# Indicator_voltage_TNN_V1_0.net
KiCad netlist of a schematic drawn in EAGLE
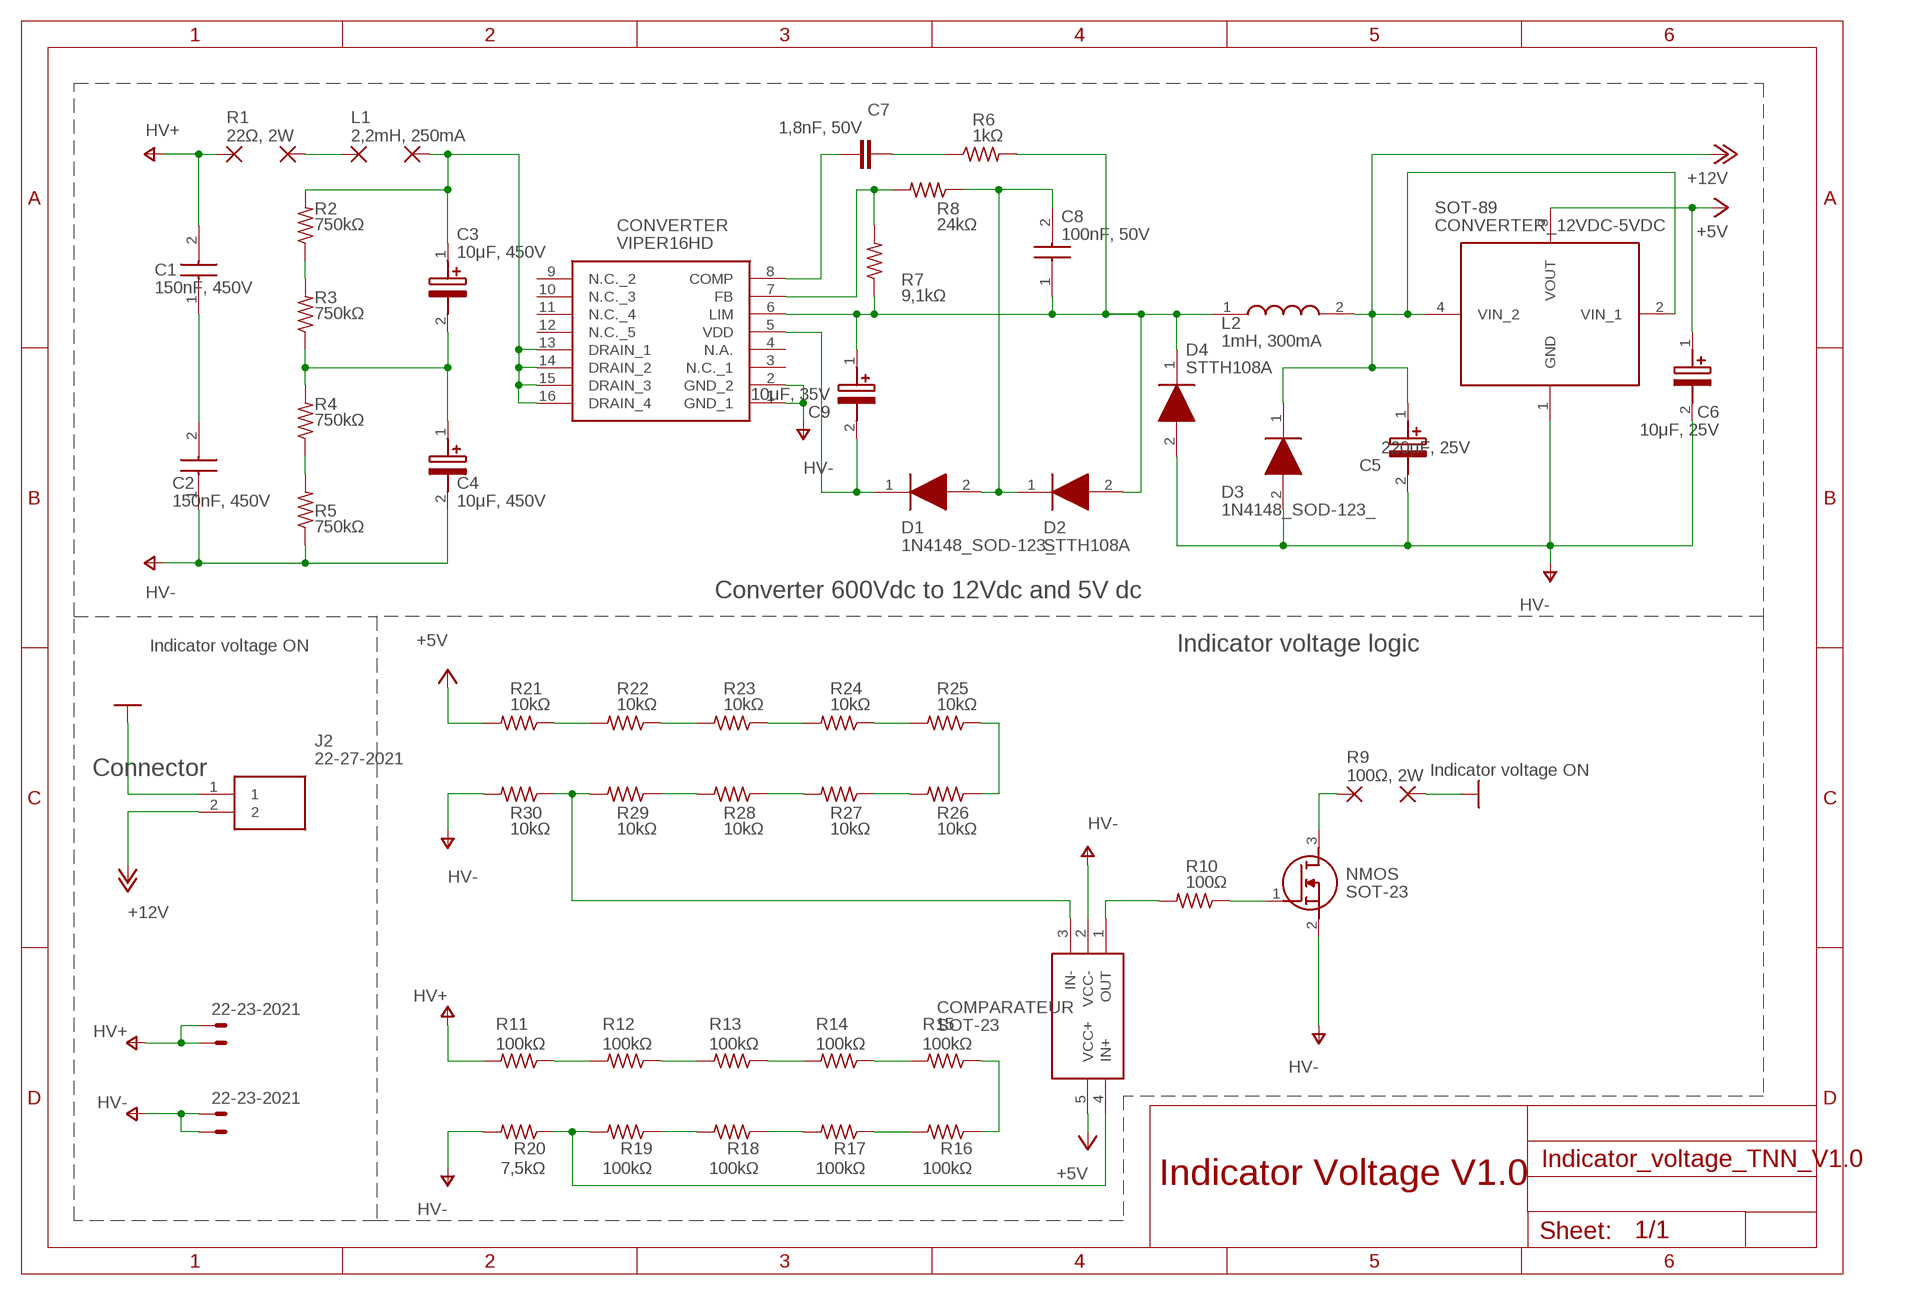
[diagram p0: schematic, sheet 1]

(export (version "E")
  (design (tool "Eeschema 10.0.6"))
  (components
    (comp (ref "C1")
      (value "150nF, 450V")
      (footprint "eagle-import:CAPC4720X175N")
      (fields
        (field (name "ARROW_PART_NUMBER") "C1808W154KCRACTU")
        (field (name "MOUSER_PART_NUMBER") "80-C1808W154KCR")
      )
      (libsource (lib "eagle-import") (part "C1808W154KCRACTU"))
    )
    (comp (ref "C2")
      (value "150nF, 450V")
      (footprint "eagle-import:CAPC4720X175N")
      (fields
        (field (name "ARROW_PART_NUMBER") "C1808W154KCRACTU")
        (field (name "MOUSER_PART_NUMBER") "80-C1808W154KCR")
      )
      (libsource (lib "eagle-import") (part "C1808W154KCRACTU"))
    )
    (comp (ref "C3")
      (value "10μF, 450V")
      (footprint "eagle-import:CAPPRD500W60D1300H2250")
      (fields (field (name "MANUFACTURER_PART_NUMBER") "7112129"))
      (libsource (lib "eagle-import") (part "7112129"))
    )
    (comp (ref "C4")
      (value "10μF, 450V")
      (footprint "eagle-import:CAPPRD500W60D1300H2250")
      (fields (field (name "MANUFACTURER_PART_NUMBER") "7112129"))
      (libsource (lib "eagle-import") (part "7112129"))
    )
    (comp (ref "C5")
      (value "220μF, 25V")
      (footprint "eagle-import:CAPPRD500W60D1300H2250")
      (fields (field (name "MANUFACTURER_PART_NUMBER") "7112129"))
      (libsource (lib "eagle-import") (part "7112129"))
    )
    (comp (ref "C6")
      (value "10μF, 25V")
      (footprint "eagle-import:CAPPRD200W55D525H1200")
      (fields (field (name "MANUFACTURER_PART_NUMBER") "ECA1VM100"))
      (libsource (lib "eagle-import") (part "ECA1VM100"))
    )
    (comp (ref "C7")
      (value "1,8nF, 50V")
      (footprint "eagle-import:C0805")
      (libsource (lib "eagle-import") (part "C-EUC0805"))
    )
    (comp (ref "C8")
      (value "100nF, 50V")
      (footprint "eagle-import:CAPC2012X88N")
      (fields
        (field (name "ARROW_PART_NUMBER") "C0805C104K5RACTU")
        (field (name "MOUSER_PART_NUMBER") "80-C0805C104K5R")
      )
      (libsource (lib "eagle-import") (part "C0805C104K5RACTU"))
    )
    (comp (ref "C9")
      (value "10μF, 35V")
      (footprint "eagle-import:CAPPRD200W55D525H1200")
      (fields (field (name "MANUFACTURER_PART_NUMBER") "ECA1VM100"))
      (libsource (lib "eagle-import") (part "ECA1VM100"))
    )
    (comp (ref "COMPARATEUR")
      (value "SOT-23")
      (footprint "eagle-import:SOT95P280X145-5N")
      (fields
        (field (name "ARROW_PART_NUMBER") "TS391IYLT")
        (field (name "MOUSER_PART_NUMBER") "511-TS391IYLT")
      )
      (libsource (lib "eagle-import") (part "TS391IYLT"))
    )
    (comp (ref "CONVERTER")
      (value "VIPER16HD")
      (footprint "eagle-import:SOIC127P600X175-16N")
      (fields (field (name "MOUSER_PART_NUMBER") "511-VIPER16HD"))
      (libsource (lib "eagle-import") (part "VIPER16HD"))
    )
    (comp (ref "CONVERTER_12VDC-5VDC")
      (value "SOT-89")
      (footprint "eagle-import:ST-SOT-89")
      (fields
        (field (name "ARROW_PART_NUMBER") "LDK320ADU120R")
        (field (name "MOUSER_PART_NUMBER") "511-LDK320ADU120R")
      )
      (libsource (lib "eagle-import") (part "LDK320ADU120R"))
    )
    (comp (ref "D1")
      (value "1N4148_SOD-123_")
      (footprint "eagle-import:SOD3716X135N")
      (fields (field (name "MANUFACTURER_PART_NUMBER") "1N4148(SOD-123)"))
      (libsource (lib "eagle-import") (part "1N4148_SOD-123_"))
    )
    (comp (ref "D2")
      (value "STTH108A")
      (footprint "eagle-import:DIOM5126X265N")
      (fields (field (name "MOUSER_PART_NUMBER") "511-STTH108A"))
      (libsource (lib "eagle-import") (part "STTH108A"))
    )
    (comp (ref "D3")
      (value "1N4148_SOD-123_")
      (footprint "eagle-import:SOD3716X135N")
      (fields (field (name "MANUFACTURER_PART_NUMBER") "1N4148(SOD-123)"))
      (libsource (lib "eagle-import") (part "1N4148_SOD-123_"))
    )
    (comp (ref "D4")
      (value "STTH108A")
      (footprint "eagle-import:DIOM5126X265N")
      (fields (field (name "MOUSER_PART_NUMBER") "511-STTH108A"))
      (libsource (lib "eagle-import") (part "STTH108A"))
    )
    (comp (ref "HV+")
      (value "22-23-2021")
      (footprint "eagle-import:22-23-2021")
      (fields (field (name "MF") "MOLEX"))
      (libsource (lib "eagle-import") (part "22-23-2021"))
    )
    (comp (ref "HV-")
      (value "22-23-2021")
      (footprint "eagle-import:22-23-2021")
      (fields (field (name "MF") "MOLEX"))
      (libsource (lib "eagle-import") (part "22-23-2021"))
    )
    (comp (ref "J2")
      (value "22-27-2021")
      (footprint "eagle-import:SHDR2W64P0X254_1X2_508X580X117")
      (fields (field (name "MOUSER_PART_NUMBER") "538-22-27-2021"))
      (libsource (lib "eagle-import") (part "22-27-2021"))
    )
    (comp (ref "L1")
      (value "2,2mH, 250mA")
      (footprint "eagle-import:1,6_0,8")
      (libsource (lib "eagle-import") (part "1,6/0,8"))
    )
    (comp (ref "L2")
      (value "1mH, 300mA")
      (footprint "eagle-import:RLB0914")
      (fields
        (field (name "ARROW_PART_NUMBER") "RLB0914-102KL")
        (field (name "MOUSER_PART_NUMBER") "652-RLB0914-102KL")
      )
      (libsource (lib "eagle-import") (part "RLB0914-102KL"))
    )
    (comp (ref "L3")
      (value "2,2mH, 250mA")
      (footprint "eagle-import:1,6_0,8")
      (libsource (lib "eagle-import") (part "1,6/0,8"))
    )
    (comp (ref "NMOS")
      (value "SOT-23")
      (footprint "eagle-import:SOT96P240X110-3N")
      (fields
        (field (name "ARROW_PART_NUMBER") "DMN2041L-7")
        (field (name "MOUSER_PART_NUMBER") "621-DMN2041L-7")
      )
      (libsource (lib "eagle-import") (part "DMN2041L-7"))
    )
    (comp (ref "PAD2")
      (value "1,6/0,8")
      (footprint "eagle-import:1,6_0,8")
      (libsource (lib "eagle-import") (part "1,6/0,8"))
    )
    (comp (ref "PAD4")
      (value "1,6/0,8")
      (footprint "eagle-import:1,6_0,8")
      (libsource (lib "eagle-import") (part "1,6/0,8"))
    )
    (comp (ref "R1")
      (value "22Ω, 2W")
      (footprint "eagle-import:1,6_0,8")
      (libsource (lib "eagle-import") (part "1,6/0,8"))
    )
    (comp (ref "R2")
      (value "750kΩ")
      (footprint "eagle-import:M3216")
      (libsource (lib "eagle-import") (part "R-US_M3216"))
    )
    (comp (ref "R3")
      (value "750kΩ")
      (footprint "eagle-import:M3216")
      (libsource (lib "eagle-import") (part "R-US_M3216"))
    )
    (comp (ref "R4")
      (value "750kΩ")
      (footprint "eagle-import:M3216")
      (libsource (lib "eagle-import") (part "R-US_M3216"))
    )
    (comp (ref "R5")
      (value "750kΩ")
      (footprint "eagle-import:M3216")
      (libsource (lib "eagle-import") (part "R-US_M3216"))
    )
    (comp (ref "R6")
      (value "1kΩ")
      (footprint "eagle-import:M2012")
      (libsource (lib "eagle-import") (part "R-US_M2012"))
    )
    (comp (ref "R7")
      (value "9,1kΩ")
      (footprint "eagle-import:M2012")
      (libsource (lib "eagle-import") (part "R-US_M2012"))
    )
    (comp (ref "R8")
      (value "24kΩ")
      (footprint "eagle-import:M2012")
      (libsource (lib "eagle-import") (part "R-US_M2012"))
    )
    (comp (ref "R9")
      (value "100Ω, 2W")
      (footprint "eagle-import:1,6_0,8")
      (libsource (lib "eagle-import") (part "1,6/0,8"))
    )
    (comp (ref "R10")
      (value "100Ω")
      (footprint "eagle-import:R0603")
      (libsource (lib "eagle-import") (part "R-US_R0603"))
    )
    (comp (ref "R11")
      (value "100kΩ")
      (footprint "eagle-import:R0603")
      (libsource (lib "eagle-import") (part "R-US_R0603"))
    )
    (comp (ref "R12")
      (value "100kΩ")
      (footprint "eagle-import:R0603")
      (libsource (lib "eagle-import") (part "R-US_R0603"))
    )
    (comp (ref "R13")
      (value "100kΩ")
      (footprint "eagle-import:R0603")
      (libsource (lib "eagle-import") (part "R-US_R0603"))
    )
    (comp (ref "R14")
      (value "100kΩ")
      (footprint "eagle-import:R0603")
      (libsource (lib "eagle-import") (part "R-US_R0603"))
    )
    (comp (ref "R15")
      (value "100kΩ")
      (footprint "eagle-import:R0603")
      (libsource (lib "eagle-import") (part "R-US_R0603"))
    )
    (comp (ref "R16")
      (value "100kΩ")
      (footprint "eagle-import:R0603")
      (libsource (lib "eagle-import") (part "R-US_R0603"))
    )
    (comp (ref "R17")
      (value "100kΩ")
      (footprint "eagle-import:R0603")
      (libsource (lib "eagle-import") (part "R-US_R0603"))
    )
    (comp (ref "R18")
      (value "100kΩ")
      (footprint "eagle-import:R0603")
      (libsource (lib "eagle-import") (part "R-US_R0603"))
    )
    (comp (ref "R19")
      (value "100kΩ")
      (footprint "eagle-import:R0603")
      (libsource (lib "eagle-import") (part "R-US_R0603"))
    )
    (comp (ref "R20")
      (value "7,5kΩ")
      (footprint "eagle-import:R0603")
      (libsource (lib "eagle-import") (part "R-US_R0603"))
    )
    (comp (ref "R21")
      (value "10kΩ")
      (footprint "eagle-import:R0603")
      (libsource (lib "eagle-import") (part "R-US_R0603"))
    )
    (comp (ref "R22")
      (value "10kΩ")
      (footprint "eagle-import:R0603")
      (libsource (lib "eagle-import") (part "R-US_R0603"))
    )
    (comp (ref "R23")
      (value "10kΩ")
      (footprint "eagle-import:R0603")
      (libsource (lib "eagle-import") (part "R-US_R0603"))
    )
    (comp (ref "R24")
      (value "10kΩ")
      (footprint "eagle-import:R0603")
      (libsource (lib "eagle-import") (part "R-US_R0603"))
    )
    (comp (ref "R25")
      (value "10kΩ")
      (footprint "eagle-import:R0603")
      (libsource (lib "eagle-import") (part "R-US_R0603"))
    )
    (comp (ref "R26")
      (value "10kΩ")
      (footprint "eagle-import:R0603")
      (libsource (lib "eagle-import") (part "R-US_R0603"))
    )
    (comp (ref "R27")
      (value "10kΩ")
      (footprint "eagle-import:R0603")
      (libsource (lib "eagle-import") (part "R-US_R0603"))
    )
    (comp (ref "R28")
      (value "10kΩ")
      (footprint "eagle-import:R0603")
      (libsource (lib "eagle-import") (part "R-US_R0603"))
    )
    (comp (ref "R29")
      (value "10kΩ")
      (footprint "eagle-import:R0603")
      (libsource (lib "eagle-import") (part "R-US_R0603"))
    )
    (comp (ref "R30")
      (value "10kΩ")
      (footprint "eagle-import:R0603")
      (libsource (lib "eagle-import") (part "R-US_R0603"))
    )
  )
  (nets
    (net (code "1") (name "+5V") (class "Default")
      (node (ref "C6") (pin "1") (pinfunction "+_1") (pintype "bidirectional"))
      (node (ref "COMPARATEUR") (pin "5") (pinfunction "VCC+_5") (pintype "bidirectional"))
      (node (ref "CONVERTER_12VDC-5VDC") (pin "3") (pinfunction "VOUT_3") (pintype "bidirectional"))
      (node (ref "R21") (pin "2") (pinfunction "2_2") (pintype "passive"))
    )
    (net (code "2") (name "+12V") (class "Default")
      (node (ref "C5") (pin "1") (pinfunction "+_1") (pintype "bidirectional"))
      (node (ref "CONVERTER_12VDC-5VDC") (pin "2") (pinfunction "VIN_1_2") (pintype "bidirectional"))
      (node (ref "CONVERTER_12VDC-5VDC") (pin "4") (pinfunction "VIN_2_4") (pintype "bidirectional"))
      (node (ref "D3") (pin "1") (pinfunction "K_1") (pintype "bidirectional"))
      (node (ref "J2") (pin "2") (pinfunction "2_2") (pintype "bidirectional"))
      (node (ref "L2") (pin "2") (pinfunction "2_2") (pintype "bidirectional"))
    )
    (net (code "3") (name "HV+") (class "Default")
      (node (ref "C1") (pin "2") (pinfunction "2_2") (pintype "bidirectional"))
      (node (ref "HV+") (pin "1") (pinfunction "S_1") (pintype "passive"))
      (node (ref "HV+") (pin "2") (pinfunction "S_2") (pintype "passive"))
      (node (ref "R1") (pin "1") (pinfunction "P_1") (pintype "passive"))
      (node (ref "R11") (pin "2") (pinfunction "2_2") (pintype "passive"))
    )
    (net (code "4") (name "HV-") (class "Default")
      (node (ref "C2") (pin "1") (pinfunction "1_1") (pintype "bidirectional"))
      (node (ref "C4") (pin "2") (pinfunction "-_2") (pintype "bidirectional"))
      (node (ref "C5") (pin "2") (pinfunction "-_2") (pintype "bidirectional"))
      (node (ref "C6") (pin "2") (pinfunction "-_2") (pintype "bidirectional"))
      (node (ref "COMPARATEUR") (pin "2") (pinfunction "VCC-_2") (pintype "bidirectional"))
      (node (ref "CONVERTER") (pin "1") (pinfunction "GND_1_1") (pintype "bidirectional"))
      (node (ref "CONVERTER") (pin "2") (pinfunction "GND_2_2") (pintype "bidirectional"))
      (node (ref "CONVERTER_12VDC-5VDC") (pin "1") (pinfunction "GND_1") (pintype "bidirectional"))
      (node (ref "D3") (pin "2") (pinfunction "A_2") (pintype "bidirectional"))
      (node (ref "D4") (pin "2") (pinfunction "A_2") (pintype "bidirectional"))
      (node (ref "HV-") (pin "1") (pinfunction "S_1") (pintype "passive"))
      (node (ref "HV-") (pin "2") (pinfunction "S_2") (pintype "passive"))
      (node (ref "NMOS") (pin "2") (pinfunction "S_2") (pintype "bidirectional"))
      (node (ref "R20") (pin "2") (pinfunction "2_2") (pintype "passive"))
      (node (ref "R30") (pin "2") (pinfunction "2_2") (pintype "passive"))
      (node (ref "R5") (pin "1") (pinfunction "1_1") (pintype "passive"))
    )
    (net (code "5") (name "Indicator voltage ON") (class "Default")
      (node (ref "J2") (pin "1") (pinfunction "1_1") (pintype "bidirectional"))
      (node (ref "PAD4") (pin "1") (pinfunction "P_1") (pintype "passive"))
    )
    (net (code "6") (name "Net-(C1-Pad1)") (class "Default")
      (node (ref "C1") (pin "1") (pinfunction "1_1") (pintype "bidirectional"))
      (node (ref "C2") (pin "2") (pinfunction "2_2") (pintype "bidirectional"))
    )
    (net (code "7") (name "Net-(C3-+)") (class "Default")
      (node (ref "C3") (pin "1") (pinfunction "+_1") (pintype "bidirectional"))
      (node (ref "CONVERTER") (pin "13") (pinfunction "DRAIN_1_13") (pintype "bidirectional"))
      (node (ref "CONVERTER") (pin "14") (pinfunction "DRAIN_2_14") (pintype "bidirectional"))
      (node (ref "CONVERTER") (pin "15") (pinfunction "DRAIN_3_15") (pintype "bidirectional"))
      (node (ref "CONVERTER") (pin "16") (pinfunction "DRAIN_4_16") (pintype "bidirectional"))
      (node (ref "L3") (pin "1") (pinfunction "P_1") (pintype "passive"))
      (node (ref "R2") (pin "2") (pinfunction "2_2") (pintype "passive"))
    )
    (net (code "8") (name "Net-(C3--)") (class "Default")
      (node (ref "C3") (pin "2") (pinfunction "-_2") (pintype "bidirectional"))
      (node (ref "C4") (pin "1") (pinfunction "+_1") (pintype "bidirectional"))
      (node (ref "R3") (pin "1") (pinfunction "1_1") (pintype "passive"))
      (node (ref "R4") (pin "2") (pinfunction "2_2") (pintype "passive"))
    )
    (net (code "9") (name "Net-(C7-Pad1)") (class "Default")
      (node (ref "C7") (pin "1") (pinfunction "1_1") (pintype "passive"))
      (node (ref "R6") (pin "1") (pinfunction "1_1") (pintype "passive"))
    )
    (net (code "10") (name "Net-(C9-+)") (class "Default")
      (node (ref "C8") (pin "1") (pinfunction "1_1") (pintype "bidirectional"))
      (node (ref "C9") (pin "1") (pinfunction "+_1") (pintype "bidirectional"))
      (node (ref "CONVERTER") (pin "6") (pinfunction "LIM_6") (pintype "bidirectional"))
      (node (ref "D2") (pin "2") (pinfunction "A_2") (pintype "bidirectional"))
      (node (ref "D4") (pin "1") (pinfunction "K_1") (pintype "bidirectional"))
      (node (ref "L2") (pin "1") (pinfunction "1_1") (pintype "bidirectional"))
      (node (ref "R6") (pin "2") (pinfunction "2_2") (pintype "passive"))
      (node (ref "R7") (pin "1") (pinfunction "1_1") (pintype "passive"))
    )
    (net (code "11") (name "Net-(C9--)") (class "Default")
      (node (ref "C9") (pin "2") (pinfunction "-_2") (pintype "bidirectional"))
      (node (ref "CONVERTER") (pin "5") (pinfunction "VDD_5") (pintype "bidirectional"))
      (node (ref "D1") (pin "1") (pinfunction "K_1") (pintype "bidirectional"))
    )
    (net (code "12") (name "Net-(COMPARATEUR-IN+)") (class "Default")
      (node (ref "COMPARATEUR") (pin "4") (pinfunction "IN+_4") (pintype "bidirectional"))
      (node (ref "R19") (pin "2") (pinfunction "2_2") (pintype "passive"))
      (node (ref "R20") (pin "1") (pinfunction "1_1") (pintype "passive"))
    )
    (net (code "13") (name "Net-(COMPARATEUR-IN-)") (class "Default")
      (node (ref "COMPARATEUR") (pin "3") (pinfunction "IN-_3") (pintype "bidirectional"))
      (node (ref "R29") (pin "2") (pinfunction "2_2") (pintype "passive"))
      (node (ref "R30") (pin "1") (pinfunction "1_1") (pintype "passive"))
    )
    (net (code "14") (name "Net-(COMPARATEUR-OUT)") (class "Default")
      (node (ref "COMPARATEUR") (pin "1") (pinfunction "OUT_1") (pintype "bidirectional"))
      (node (ref "R10") (pin "2") (pinfunction "2_2") (pintype "passive"))
    )
    (net (code "15") (name "Net-(CONVERTER-COMP)") (class "Default")
      (node (ref "C7") (pin "2") (pinfunction "2_2") (pintype "passive"))
      (node (ref "CONVERTER") (pin "8") (pinfunction "COMP_8") (pintype "bidirectional"))
    )
    (net (code "16") (name "Net-(CONVERTER-FB)") (class "Default")
      (node (ref "CONVERTER") (pin "7") (pinfunction "FB_7") (pintype "bidirectional"))
      (node (ref "R7") (pin "2") (pinfunction "2_2") (pintype "passive"))
      (node (ref "R8") (pin "2") (pinfunction "2_2") (pintype "passive"))
    )
    (net (code "17") (name "Net-(D1-A)") (class "Default")
      (node (ref "C8") (pin "2") (pinfunction "2_2") (pintype "bidirectional"))
      (node (ref "D1") (pin "2") (pinfunction "A_2") (pintype "bidirectional"))
      (node (ref "D2") (pin "1") (pinfunction "K_1") (pintype "bidirectional"))
      (node (ref "R8") (pin "1") (pinfunction "1_1") (pintype "passive"))
    )
    (net (code "18") (name "Net-(L1-P)") (class "Default")
      (node (ref "L1") (pin "1") (pinfunction "P_1") (pintype "passive"))
      (node (ref "PAD2") (pin "1") (pinfunction "P_1") (pintype "passive"))
    )
    (net (code "19") (name "Net-(NMOS-D)") (class "Default")
      (node (ref "NMOS") (pin "3") (pinfunction "D_3") (pintype "bidirectional"))
      (node (ref "R9") (pin "1") (pinfunction "P_1") (pintype "passive"))
    )
    (net (code "20") (name "Net-(NMOS-G)") (class "Default")
      (node (ref "NMOS") (pin "1") (pinfunction "G_1") (pintype "bidirectional"))
      (node (ref "R10") (pin "1") (pinfunction "1_1") (pintype "passive"))
    )
    (net (code "21") (name "Net-(R2-Pad1)") (class "Default")
      (node (ref "R2") (pin "1") (pinfunction "1_1") (pintype "passive"))
      (node (ref "R3") (pin "2") (pinfunction "2_2") (pintype "passive"))
    )
    (net (code "22") (name "Net-(R4-Pad1)") (class "Default")
      (node (ref "R4") (pin "1") (pinfunction "1_1") (pintype "passive"))
      (node (ref "R5") (pin "2") (pinfunction "2_2") (pintype "passive"))
    )
    (net (code "23") (name "Net-(R11-Pad1)") (class "Default")
      (node (ref "R11") (pin "1") (pinfunction "1_1") (pintype "passive"))
      (node (ref "R12") (pin "2") (pinfunction "2_2") (pintype "passive"))
    )
    (net (code "24") (name "Net-(R12-Pad1)") (class "Default")
      (node (ref "R12") (pin "1") (pinfunction "1_1") (pintype "passive"))
      (node (ref "R13") (pin "2") (pinfunction "2_2") (pintype "passive"))
    )
    (net (code "25") (name "Net-(R13-Pad1)") (class "Default")
      (node (ref "R13") (pin "1") (pinfunction "1_1") (pintype "passive"))
      (node (ref "R14") (pin "2") (pinfunction "2_2") (pintype "passive"))
    )
    (net (code "26") (name "Net-(R14-Pad1)") (class "Default")
      (node (ref "R14") (pin "1") (pinfunction "1_1") (pintype "passive"))
      (node (ref "R15") (pin "2") (pinfunction "2_2") (pintype "passive"))
    )
    (net (code "27") (name "Net-(R15-Pad1)") (class "Default")
      (node (ref "R15") (pin "1") (pinfunction "1_1") (pintype "passive"))
      (node (ref "R16") (pin "1") (pinfunction "1_1") (pintype "passive"))
    )
    (net (code "28") (name "Net-(R16-Pad2)") (class "Default")
      (node (ref "R16") (pin "2") (pinfunction "2_2") (pintype "passive"))
      (node (ref "R17") (pin "1") (pinfunction "1_1") (pintype "passive"))
    )
    (net (code "29") (name "Net-(R17-Pad2)") (class "Default")
      (node (ref "R17") (pin "2") (pinfunction "2_2") (pintype "passive"))
      (node (ref "R18") (pin "1") (pinfunction "1_1") (pintype "passive"))
    )
    (net (code "30") (name "Net-(R18-Pad2)") (class "Default")
      (node (ref "R18") (pin "2") (pinfunction "2_2") (pintype "passive"))
      (node (ref "R19") (pin "1") (pinfunction "1_1") (pintype "passive"))
    )
    (net (code "31") (name "Net-(R21-Pad1)") (class "Default")
      (node (ref "R21") (pin "1") (pinfunction "1_1") (pintype "passive"))
      (node (ref "R22") (pin "2") (pinfunction "2_2") (pintype "passive"))
    )
    (net (code "32") (name "Net-(R22-Pad1)") (class "Default")
      (node (ref "R22") (pin "1") (pinfunction "1_1") (pintype "passive"))
      (node (ref "R23") (pin "2") (pinfunction "2_2") (pintype "passive"))
    )
    (net (code "33") (name "Net-(R23-Pad1)") (class "Default")
      (node (ref "R23") (pin "1") (pinfunction "1_1") (pintype "passive"))
      (node (ref "R24") (pin "2") (pinfunction "2_2") (pintype "passive"))
    )
    (net (code "34") (name "Net-(R24-Pad1)") (class "Default")
      (node (ref "R24") (pin "1") (pinfunction "1_1") (pintype "passive"))
      (node (ref "R25") (pin "2") (pinfunction "2_2") (pintype "passive"))
    )
    (net (code "35") (name "Net-(R25-Pad1)") (class "Default")
      (node (ref "R25") (pin "1") (pinfunction "1_1") (pintype "passive"))
      (node (ref "R26") (pin "1") (pinfunction "1_1") (pintype "passive"))
    )
    (net (code "36") (name "Net-(R26-Pad2)") (class "Default")
      (node (ref "R26") (pin "2") (pinfunction "2_2") (pintype "passive"))
      (node (ref "R27") (pin "1") (pinfunction "1_1") (pintype "passive"))
    )
    (net (code "37") (name "Net-(R27-Pad2)") (class "Default")
      (node (ref "R27") (pin "2") (pinfunction "2_2") (pintype "passive"))
      (node (ref "R28") (pin "1") (pinfunction "1_1") (pintype "passive"))
    )
    (net (code "38") (name "Net-(R28-Pad2)") (class "Default")
      (node (ref "R28") (pin "2") (pinfunction "2_2") (pintype "passive"))
      (node (ref "R29") (pin "1") (pinfunction "1_1") (pintype "passive"))
    )
    (net (code "39") (name "unconnected-(CONVERTER-N.A.-Pad4)") (class "Default")
      (node (ref "CONVERTER") (pin "4") (pinfunction "N.A._4") (pintype "bidirectional"))
    )
    (net (code "40") (name "unconnected-(CONVERTER-N.C._1-Pad3)") (class "Default")
      (node (ref "CONVERTER") (pin "3") (pinfunction "N.C._1_3") (pintype "bidirectional"))
    )
    (net (code "41") (name "unconnected-(CONVERTER-N.C._2-Pad9)") (class "Default")
      (node (ref "CONVERTER") (pin "9") (pinfunction "N.C._2_9") (pintype "bidirectional"))
    )
    (net (code "42") (name "unconnected-(CONVERTER-N.C._3-Pad10)") (class "Default")
      (node (ref "CONVERTER") (pin "10") (pinfunction "N.C._3_10") (pintype "bidirectional"))
    )
    (net (code "43") (name "unconnected-(CONVERTER-N.C._4-Pad11)") (class "Default")
      (node (ref "CONVERTER") (pin "11") (pinfunction "N.C._4_11") (pintype "bidirectional"))
    )
    (net (code "44") (name "unconnected-(CONVERTER-N.C._5-Pad12)") (class "Default")
      (node (ref "CONVERTER") (pin "12") (pinfunction "N.C._5_12") (pintype "bidirectional"))
    )
  )
)
